# Power_section.net
KiCad netlist of a schematic drawn in Altium Designer
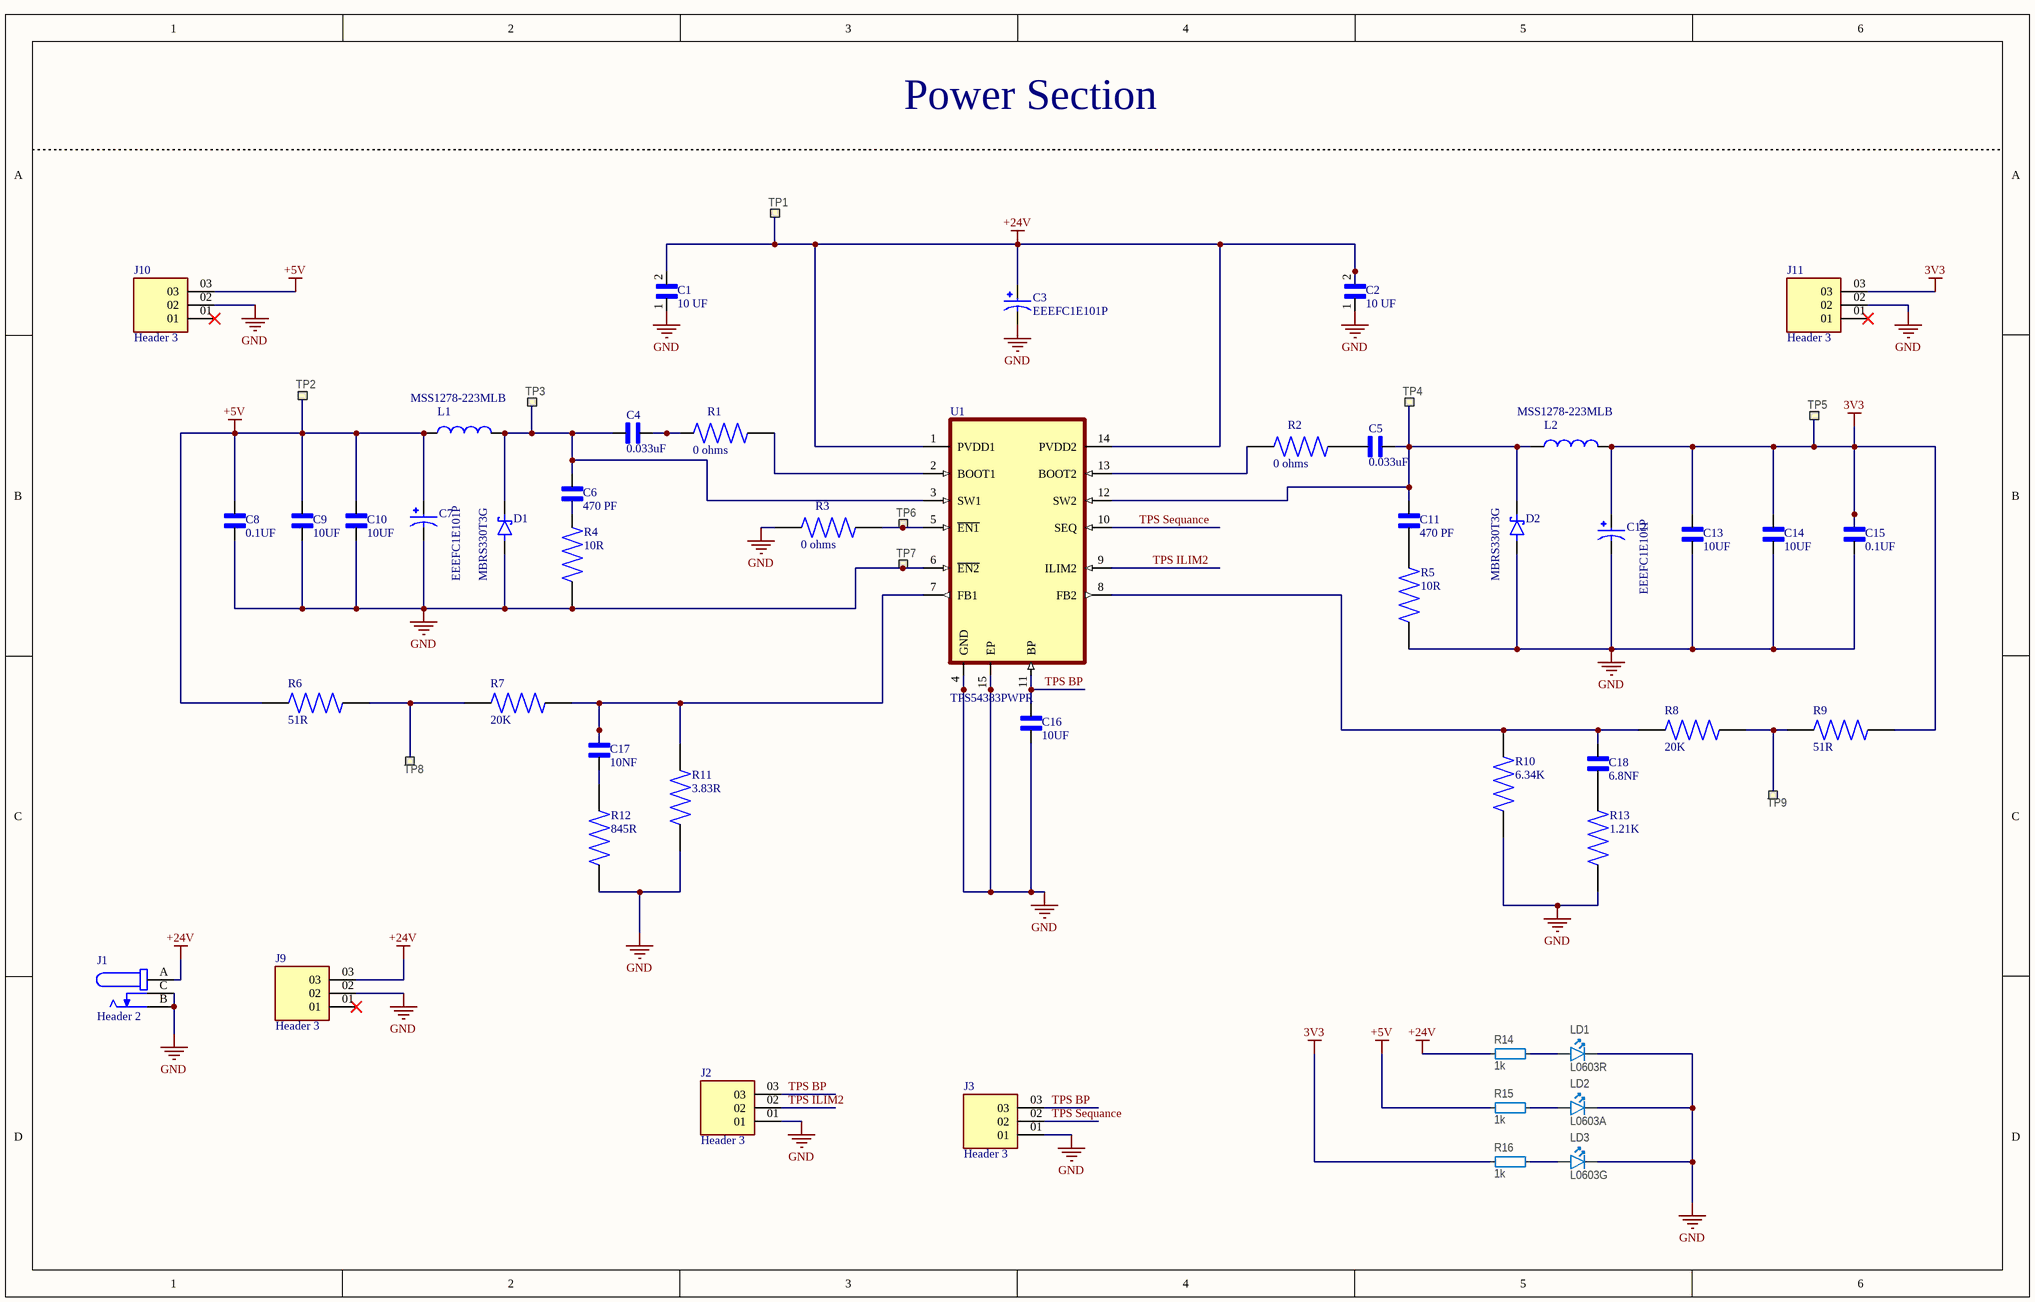
[diagram p0: Power section.SchDoc]

(export (version "E")
  (design (tool "Eeschema 10.0.6"))
  (components
    (comp (ref "C1")
      (value "10 UF")
      (footprint "CAPC3216X180N")
      (description "10礔 卤20% 25V Ceramic Capacitor 1206 (3216 Metric)")
      (fields (field (name "MF") "TDK") (field (name "DIGI-KEY_PART_NUMBER") "445-7708-2-ND"))
      (libsource (lib "C3216X5R1E106M160AB") (part "C3216X5R1E106M160AB"))
    )
    (comp (ref "C2")
      (value "10 UF")
      (footprint "CAPC3216X180N")
      (description "10礔 卤20% 25V Ceramic Capacitor 1206 (3216 Metric)")
      (fields (field (name "MF") "TDK") (field (name "DIGI-KEY_PART_NUMBER") "445-7708-2-ND"))
      (libsource (lib "C3216X5R1E106M160AB") (part "C3216X5R1E106M160AB"))
    )
    (comp (ref "C3")
      (value "EEEFC1E101P")
      (footprint "CAP_EEEFC1E101P")
      (fields (field (name "MF") "Panasonic") (field (name "MP") "EEE-FC1E101P"))
      (libsource (lib "EEEFC1E101P") (part "EEEFC1E101P"))
    )
    (comp (ref "C4")
      (value "0.033uF")
      (footprint "CAPC1608X90")
      (description "Capacitor, ceramic, 25 V, X7R, 20%, .033 μF, 0603")
      (fields (field (name "MF") "KEMET") (field (name "MP") "C0603C104J3RACTU"))
      (libsource (lib "") (part "C0603C104J3RACTU_1"))
    )
    (comp (ref "C5")
      (value "0.033uF")
      (footprint "CAPC1608X90")
      (description "Capacitor, ceramic, 25 V, X7R, 20%, .033 μF, 0603")
      (fields (field (name "MF") "KEMET") (field (name "MP") "C0603C104J3RACTU"))
      (libsource (lib "") (part "C0603C104J3RACTU_1"))
    )
    (comp (ref "C6")
      (value "470 PF")
      (footprint "CAPC1608X90")
      (description "Capacitor, ceramic, 25 V, X7R, 20%, 470 pF, 0603")
      (fields (field (name "MF") "KEMET") (field (name "MP") "C0603C104J3RACTU"))
      (libsource (lib "Accelo Integrated_Library") (part "C0603C104J3RACTU"))
    )
    (comp (ref "C7")
      (value "EEEFC1E101P")
      (footprint "CAP_EEEFC1E101P")
      (fields (field (name "MF") "Panasonic") (field (name "MP") "EEE-FC1E101P"))
      (libsource (lib "EEEFC1E101P") (part "EEEFC1E101P"))
    )
    (comp (ref "C8")
      (value "0.1UF")
      (footprint "CAPC1608X90")
      (description "Capacitor, ceramic, 10 V, X7R, 20%, 0.1 μF, 0603")
      (fields (field (name "MF") "KEMET") (field (name "MP") "C0603C104J3RACTU"))
      (libsource (lib "Accelo Integrated_Library") (part "C0603C104J3RACTU"))
    )
    (comp (ref "C9")
      (value "10UF")
      (footprint "CAPC2012X140N")
      (description "Capacitor, ceramic, 6.3 V, X5R, 20%, 10 μF, 0805")
      (fields (field (name "MF") "AVX") (field (name "MP") "0805ZD474MAT2A"))
      (libsource (lib "0805ZD474MAT2A") (part "0805ZD474MAT2A"))
    )
    (comp (ref "C10")
      (value "10UF")
      (footprint "CAPC2012X140N")
      (description "Capacitor, ceramic, 6.3 V, X5R, 20%, 10 μF, 0805")
      (fields (field (name "MF") "AVX") (field (name "MP") "0805ZD474MAT2A"))
      (libsource (lib "0805ZD474MAT2A") (part "0805ZD474MAT2A"))
    )
    (comp (ref "C11")
      (value "470 PF")
      (footprint "CAPC1608X90")
      (description "Capacitor, ceramic, 25 V, X7R, 20%, 470 pF, 0603")
      (fields (field (name "MF") "KEMET") (field (name "MP") "C0603C104J3RACTU"))
      (libsource (lib "Accelo Integrated_Library") (part "C0603C104J3RACTU"))
    )
    (comp (ref "C12")
      (value "EEEFC1E101P")
      (footprint "CAP_EEEFC1E101P")
      (fields (field (name "MF") "Panasonic") (field (name "MP") "EEE-FC1E101P"))
      (libsource (lib "EEEFC1E101P") (part "EEEFC1E101P"))
    )
    (comp (ref "C13")
      (value "10UF")
      (footprint "CAPC2012X140N")
      (description "Capacitor, ceramic, 6.3 V, X5R, 20%, 10 μF, 0805")
      (fields (field (name "MF") "AVX") (field (name "MP") "0805ZD474MAT2A"))
      (libsource (lib "0805ZD474MAT2A") (part "0805ZD474MAT2A"))
    )
    (comp (ref "C14")
      (value "10UF")
      (footprint "CAPC2012X140N")
      (description "Capacitor, ceramic, 6.3 V, X5R, 20%, 10 μF, 0805")
      (fields (field (name "MF") "AVX") (field (name "MP") "0805ZD474MAT2A"))
      (libsource (lib "0805ZD474MAT2A") (part "0805ZD474MAT2A"))
    )
    (comp (ref "C15")
      (value "0.1UF")
      (footprint "CAPC1608X90")
      (description "Capacitor, ceramic, 10 V, X7R, 20%, 0.1 μF, 0603")
      (fields (field (name "MF") "KEMET") (field (name "MP") "C0603C104J3RACTU"))
      (libsource (lib "Accelo Integrated_Library") (part "C0603C104J3RACTU"))
    )
    (comp (ref "C16")
      (value "10UF")
      (footprint "CAPC2012X140N")
      (description "0.47 ÂµF Â±20% 10V Ceramic Capacitor X5R 0805 (2012 Metric)")
      (fields (field (name "MF") "AVX") (field (name "MP") "0805ZD474MAT2A"))
      (libsource (lib "0805ZD474MAT2A") (part "0805ZD474MAT2A"))
    )
    (comp (ref "C17")
      (value "10NF")
      (footprint "CAPC1608X90")
      (fields (field (name "MF") "KEMET") (field (name "MP") "C0603C104J3RACTU"))
      (libsource (lib "Accelo Integrated_Library") (part "C0603C104J3RACTU"))
    )
    (comp (ref "C18")
      (value "6.8NF")
      (footprint "CAPC1608X90")
      (fields (field (name "MF") "KEMET") (field (name "MP") "C0603C104J3RACTU"))
      (libsource (lib "Accelo Integrated_Library") (part "C0603C104J3RACTU"))
    )
    (comp (ref "D1")
      (value "MBRS330T3G")
      (footprint "DIOM7959X261N")
      (description "Diode Schottky 30 V 3A Surface Mount SMC")
      (fields (field (name "MF") "ON Semiconductor"))
      (libsource (lib "MBRS330T3G") (part "MBRS330T3G"))
    )
    (comp (ref "D2")
      (value "MBRS330T3G")
      (footprint "DIOM7959X261N")
      (description "Diode Schottky 30 V 3A Surface Mount SMC")
      (fields (field (name "MF") "ON Semiconductor"))
      (libsource (lib "MBRS330T3G") (part "MBRS330T3G"))
    )
    (comp (ref "J1")
      (value "Header 2")
      (footprint "TENSILITY_54-00129")
      (description "Connector, dc jack 5.5x2.1 mm, PCB mount, 90 degrees, silver plated, thru hole")
      (fields (field (name "MF") "Tensility International Corp") (field (name "MP") "54-00129"))
      (libsource (lib "54-00129") (part "54-00129"))
    )
    (comp (ref "J2")
      (value "Header 3")
      (footprint "SAMTEC_HMTSW-103-XX-X-S-XXX")
      (description "Connector Unshrouded Header 3 Position 2.54mm Solder Straight Through Hole")
      (fields (field (name "MF") "Samtec") (field (name "MP") "HMTSW-103-10-T-S-330"))
      (libsource (lib "Accelo Integrated_Library") (part "HMTSW-103-XX-X-S-XXX"))
    )
    (comp (ref "J3")
      (value "Header 3")
      (footprint "SAMTEC_HMTSW-103-XX-X-S-XXX")
      (description "Connector Unshrouded Header 3 Position 2.54mm Solder Straight Through Hole")
      (fields (field (name "MF") "Samtec") (field (name "MP") "HMTSW-103-10-T-S-330"))
      (libsource (lib "Accelo Integrated_Library") (part "HMTSW-103-XX-X-S-XXX"))
    )
    (comp (ref "J9")
      (value "Header 3")
      (footprint "SAMTEC_HMTSW-103-XX-X-S-XXX")
      (description "Connector Unshrouded Header 3 Position 2.54mm Solder Straight Through Hole")
      (fields (field (name "MF") "Samtec") (field (name "MP") "HMTSW-103-10-T-S-330"))
      (libsource (lib "Accelo Integrated_Library") (part "HMTSW-103-XX-X-S-XXX"))
    )
    (comp (ref "J10")
      (value "Header 3")
      (footprint "SAMTEC_HMTSW-103-XX-X-S-XXX")
      (description "Connector Unshrouded Header 3 Position 2.54mm Solder Straight Through Hole")
      (fields (field (name "MF") "Samtec") (field (name "MP") "HMTSW-103-10-T-S-330"))
      (libsource (lib "Accelo Integrated_Library") (part "HMTSW-103-XX-X-S-XXX"))
    )
    (comp (ref "J11")
      (value "Header 3")
      (footprint "SAMTEC_HMTSW-103-XX-X-S-XXX")
      (description "Connector Unshrouded Header 3 Position 2.54mm Solder Straight Through Hole")
      (fields (field (name "MF") "Samtec") (field (name "MP") "HMTSW-103-10-T-S-330"))
      (libsource (lib "Accelo Integrated_Library") (part "HMTSW-103-XX-X-S-XXX"))
    )
    (comp (ref "L1")
      (value "MSS1278-223MLB")
      (footprint "IND_MSS1278-223MLB")
      (description "Fixed Inductors 22uH Shld 20% 4A 39.5mOhms AECQ2")
      (fields (field (name "MF") "Coilcraft"))
      (libsource (lib "MSS1278-223MLB") (part "MSS1278-223MLB"))
    )
    (comp (ref "L2")
      (value "MSS1278-223MLB")
      (footprint "IND_MSS1278-223MLB")
      (description "Fixed Inductors 22uH Shld 20% 4A 39.5mOhms AECQ2")
      (fields (field (name "MF") "Coilcraft"))
      (libsource (lib "MSS1278-223MLB") (part "MSS1278-223MLB"))
    )
    (comp (ref "LD1")
      (value "L0603R")
      (footprint "LED_0603_R")
      (description "LED, Red, 0603, Vf=2V, - 40 to +100°C")
      (fields
        (field (name "PART NUMBER") "ASMT-RR45-AQ902")
        (field (name "MANUFACTURER") "Avago")
        (field (name "AUTHOR") "rsk")
      )
      (libsource (lib "pca10152") (part "ASMT-RR45-AQ902"))
    )
    (comp (ref "LD2")
      (value "L0603A")
      (footprint "LED_0603_Y")
      (description "LED, Amber, 0603,  Vf=2V, - 40 to +100°C")
      (fields
        (field (name "PART NUMBER") "ASMT-RA45-AP932")
        (field (name "MANUFACTURER") "Avago")
        (field (name "AUTHOR") "rsk")
      )
      (libsource (lib "pca10152") (part "ASMT-RA45-AP932"))
    )
    (comp (ref "LD3")
      (value "L0603G")
      (footprint "LED_0603_G")
      (description "LED, Yellow Green, 0603, Vf=2V, - 40 to +100°C")
      (fields
        (field (name "PART NUMBER") "ASMT-RF45-AN002")
        (field (name "MANUFACTURER") "Avago")
        (field (name "AUTHOR") "rsk")
      )
      (libsource (lib "pca10152") (part "ASMT-RF45-AN002"))
    )
    (comp (ref "R1")
      (value "0 ohms")
      (footprint "RESC1608X55N")
      (description "Resistor, chip, 1/16 W, 5%, 0 Ω, 0603")
      (fields (field (name "MF") "Yageo") (field (name "MP") "RC0603JR-0751RL"))
      (libsource (lib "RC0603JR-0751RL") (part "RC0603JR-0751RL"))
    )
    (comp (ref "R2")
      (value "0 ohms")
      (footprint "RESC1608X55N")
      (description "Resistor, chip, 1/16 W, 5%, 0 Ω, 0603")
      (fields (field (name "MF") "Yageo") (field (name "MP") "RC0603JR-0751RL"))
      (libsource (lib "RC0603JR-0751RL") (part "RC0603JR-0751RL"))
    )
    (comp (ref "R3")
      (value "0 ohms")
      (footprint "RESC1608X55N")
      (description "Resistor, chip, 1/16 W, 5%, 0 Ω, 0603")
      (fields (field (name "MF") "Yageo") (field (name "MP") "RC0603JR-0751RL"))
      (libsource (lib "RC0603JR-0751RL") (part "RC0603JR-0751RL"))
    )
    (comp (ref "R4")
      (value "10R")
      (footprint "RESC1608X55N")
      (description "Resistor, chip, 1/16 W, 5%, 10 Ω, 0603")
      (fields (field (name "MF") "Yageo") (field (name "MP") "RC0603JR-0751RL"))
      (libsource (lib "RC0603JR-0751RL") (part "RC0603JR-0751RL"))
    )
    (comp (ref "R5")
      (value "10R")
      (footprint "RESC1608X55N")
      (description "Resistor, chip, 1/16 W, 5%, 10 Ω, 0603")
      (fields (field (name "MF") "Yageo") (field (name "MP") "RC0603JR-0751RL"))
      (libsource (lib "RC0603JR-0751RL") (part "RC0603JR-0751RL"))
    )
    (comp (ref "R6")
      (value "51R")
      (footprint "RESC1608X55N")
      (description "51 Ohms Â±5% 0.1W, 1/10W Chip Resistor 0603 (1608 Metric) Moisture Resistant Thick Film")
      (fields (field (name "MF") "Yageo") (field (name "MP") "RC0603JR-0751RL"))
      (libsource (lib "RC0603JR-0751RL") (part "RC0603JR-0751RL"))
    )
    (comp (ref "R7")
      (value "20K")
      (footprint "RESC1608X55N")
      (description "51 Ohms Â±5% 0.1W, 1/10W Chip Resistor 0603 (1608 Metric) Moisture Resistant Thick Film")
      (fields (field (name "MF") "Yageo") (field (name "MP") "RC0603JR-0751RL"))
      (libsource (lib "RC0603JR-0751RL") (part "RC0603JR-0751RL"))
    )
    (comp (ref "R8")
      (value "20K")
      (footprint "RESC1608X55N")
      (description "51 Ohms Â±5% 0.1W, 1/10W Chip Resistor 0603 (1608 Metric) Moisture Resistant Thick Film")
      (fields (field (name "MF") "Yageo") (field (name "MP") "RC0603JR-0751RL"))
      (libsource (lib "RC0603JR-0751RL") (part "RC0603JR-0751RL"))
    )
    (comp (ref "R9")
      (value "51R")
      (footprint "RESC1608X55N")
      (description "51 Ohms Â±5% 0.1W, 1/10W Chip Resistor 0603 (1608 Metric) Moisture Resistant Thick Film")
      (fields (field (name "MF") "Yageo") (field (name "MP") "RC0603JR-0751RL"))
      (libsource (lib "RC0603JR-0751RL") (part "RC0603JR-0751RL"))
    )
    (comp (ref "R10")
      (value "6.34K")
      (footprint "RESC1608X55N")
      (description "51 Ohms Â±5% 0.1W, 1/10W Chip Resistor 0603 (1608 Metric) Moisture Resistant Thick Film")
      (fields (field (name "MF") "Yageo") (field (name "MP") "RC0603JR-0751RL"))
      (libsource (lib "RC0603JR-0751RL") (part "RC0603JR-0751RL"))
    )
    (comp (ref "R11")
      (value "3.83R")
      (footprint "RESC1608X55N")
      (description "51 Ohms Â±5% 0.1W, 1/10W Chip Resistor 0603 (1608 Metric) Moisture Resistant Thick Film")
      (fields (field (name "MF") "Yageo") (field (name "MP") "RC0603JR-0751RL"))
      (libsource (lib "RC0603JR-0751RL") (part "RC0603JR-0751RL"))
    )
    (comp (ref "R12")
      (value "845R")
      (footprint "RESC1608X55N")
      (description "51 Ohms Â±5% 0.1W, 1/10W Chip Resistor 0603 (1608 Metric) Moisture Resistant Thick Film")
      (fields (field (name "MF") "Yageo") (field (name "MP") "RC0603JR-0751RL"))
      (libsource (lib "RC0603JR-0751RL") (part "RC0603JR-0751RL"))
    )
    (comp (ref "R13")
      (value "1.21K")
      (footprint "RESC1608X55N")
      (description "51 Ohms Â±5% 0.1W, 1/10W Chip Resistor 0603 (1608 Metric) Moisture Resistant Thick Film")
      (fields (field (name "MF") "Yageo") (field (name "MP") "RC0603JR-0751RL"))
      (libsource (lib "RC0603JR-0751RL") (part "RC0603JR-0751RL"))
    )
    (comp (ref "R14")
      (value "1k")
      (footprint "RESC0603X03L_C")
      (description "Resistor, ±1%, 0.05W")
      (fields
        (field (name "PART NUMBER") "R0201-1k0")
        (field (name "MANUFACTURER") "N.A.")
        (field (name "AUTHOR") "rsk")
      )
      (libsource (lib "pca10152") (part "R0201-1k0"))
    )
    (comp (ref "R15")
      (value "1k")
      (footprint "RESC0603X03L_C")
      (description "Resistor, ±1%, 0.05W")
      (fields
        (field (name "PART NUMBER") "R0201-1k0")
        (field (name "MANUFACTURER") "N.A.")
        (field (name "AUTHOR") "rsk")
      )
      (libsource (lib "pca10152") (part "R0201-1k0"))
    )
    (comp (ref "R16")
      (value "1k")
      (footprint "RESC0603X03L_C")
      (description "Resistor, ±1%, 0.05W")
      (fields
        (field (name "PART NUMBER") "R0201-1k0")
        (field (name "MANUFACTURER") "N.A.")
        (field (name "AUTHOR") "rsk")
      )
      (libsource (lib "pca10152") (part "R0201-1k0"))
    )
    (comp (ref "TP1")
      (value "Ø0.7mm,SMD")
      (footprint "TP_SMD_D0.7mm")
      (description "0.7mm circular SMD testpad")
      (fields
        (field (name "PART NUMBER") "TP_SMD_Ø0.7MM")
        (field (name "MANUFACTURER") "Nordic Semiconductor")
        (field (name "AUTHOR") "rsk")
      )
      (libsource (lib "") (part "TP_SMD_Ø0.7MM_1"))
    )
    (comp (ref "TP2")
      (value "Ø0.7mm,SMD")
      (footprint "TP_SMD_D0.7mm")
      (description "0.7mm circular SMD testpad")
      (fields
        (field (name "PART NUMBER") "TP_SMD_Ø0.7MM")
        (field (name "MANUFACTURER") "Nordic Semiconductor")
        (field (name "AUTHOR") "rsk")
      )
      (libsource (lib "") (part "TP_SMD_Ø0.7MM_1"))
    )
    (comp (ref "TP3")
      (value "Ø0.7mm,SMD")
      (footprint "TP_SMD_D0.7mm")
      (description "0.7mm circular SMD testpad")
      (fields
        (field (name "PART NUMBER") "TP_SMD_Ø0.7MM")
        (field (name "MANUFACTURER") "Nordic Semiconductor")
        (field (name "AUTHOR") "rsk")
      )
      (libsource (lib "") (part "TP_SMD_Ø0.7MM_1"))
    )
    (comp (ref "TP4")
      (value "Ø0.7mm,SMD")
      (footprint "TP_SMD_D0.7mm")
      (description "0.7mm circular SMD testpad")
      (fields
        (field (name "PART NUMBER") "TP_SMD_Ø0.7MM")
        (field (name "MANUFACTURER") "Nordic Semiconductor")
        (field (name "AUTHOR") "rsk")
      )
      (libsource (lib "") (part "TP_SMD_Ø0.7MM_1"))
    )
    (comp (ref "TP5")
      (value "Ø0.7mm,SMD")
      (footprint "TP_SMD_D0.7mm")
      (description "0.7mm circular SMD testpad")
      (fields
        (field (name "PART NUMBER") "TP_SMD_Ø0.7MM")
        (field (name "MANUFACTURER") "Nordic Semiconductor")
        (field (name "AUTHOR") "rsk")
      )
      (libsource (lib "") (part "TP_SMD_Ø0.7MM_1"))
    )
    (comp (ref "TP6")
      (value "Ø0.7mm,SMD")
      (footprint "TP_SMD_D0.7mm")
      (description "0.7mm circular SMD testpad")
      (fields
        (field (name "PART NUMBER") "TP_SMD_Ø0.7MM")
        (field (name "MANUFACTURER") "Nordic Semiconductor")
        (field (name "AUTHOR") "rsk")
      )
      (libsource (lib "") (part "TP_SMD_Ø0.7MM_1"))
    )
    (comp (ref "TP7")
      (value "Ø0.7mm,SMD")
      (footprint "TP_SMD_D0.7mm")
      (description "0.7mm circular SMD testpad")
      (fields
        (field (name "PART NUMBER") "TP_SMD_Ø0.7MM")
        (field (name "MANUFACTURER") "Nordic Semiconductor")
        (field (name "AUTHOR") "rsk")
      )
      (libsource (lib "") (part "TP_SMD_Ø0.7MM_1"))
    )
    (comp (ref "TP8")
      (value "Ø0.7mm,SMD")
      (footprint "TP_SMD_D0.7mm")
      (description "0.7mm circular SMD testpad")
      (fields
        (field (name "PART NUMBER") "TP_SMD_Ø0.7MM")
        (field (name "MANUFACTURER") "Nordic Semiconductor")
        (field (name "AUTHOR") "rsk")
      )
      (libsource (lib "pca10152") (part "TP_SMD_Ø0.7MM"))
    )
    (comp (ref "TP9")
      (value "Ø0.7mm,SMD")
      (footprint "TP_SMD_D0.7mm")
      (description "0.7mm circular SMD testpad")
      (fields
        (field (name "PART NUMBER") "TP_SMD_Ø0.7MM")
        (field (name "MANUFACTURER") "Nordic Semiconductor")
        (field (name "AUTHOR") "rsk")
      )
      (libsource (lib "pca10152") (part "TP_SMD_Ø0.7MM"))
    )
    (comp (ref "U1")
      (value "TPS54383PWPR")
      (footprint "IC_TPS27S100BPWPR")
      (fields (field (name "MF") "{'manufacturer': u'Texas Instruments'}"))
      (libsource (lib "TP") (part "TPS54383PWPR"))
    )
  )
  (nets
    (net (code "1") (name "+5V") (class "Default")
      (node (ref "C10") (pin "1") (pinfunction "1_1") (pintype "passive"))
      (node (ref "C7") (pin "1") (pinfunction "1_1") (pintype "passive"))
      (node (ref "C8") (pin "1") (pinfunction "1_1") (pintype "passive"))
      (node (ref "C9") (pin "1") (pinfunction "1_1") (pintype "passive"))
      (node (ref "J10") (pin "03") (pinfunction "03_03") (pintype "passive"))
      (node (ref "L1") (pin "1") (pinfunction "1_1") (pintype "passive"))
      (node (ref "R15") (pin "1") (pinfunction "1_1") (pintype "passive"))
      (node (ref "R6") (pin "2") (pinfunction "2_2") (pintype "passive"))
      (node (ref "TP2") (pin "1") (pinfunction "1_1") (pintype "passive"))
    )
    (net (code "2") (name "+24V") (class "Default")
      (node (ref "C1") (pin "2") (pinfunction "2_2") (pintype "passive"))
      (node (ref "C2") (pin "2") (pinfunction "2_2") (pintype "passive"))
      (node (ref "C3") (pin "1") (pinfunction "1_1") (pintype "passive"))
      (node (ref "J1") (pin "A") (pinfunction "A_A") (pintype "passive"))
      (node (ref "J9") (pin "03") (pinfunction "03_03") (pintype "passive"))
      (node (ref "R14") (pin "1") (pinfunction "1_1") (pintype "passive"))
      (node (ref "TP1") (pin "1") (pinfunction "1_1") (pintype "passive"))
      (node (ref "U1") (pin "1") (pinfunction "PVDD1_1") (pintype "power_in"))
      (node (ref "U1") (pin "14") (pinfunction "PVDD2_14") (pintype "power_in"))
    )
    (net (code "3") (name "/TPS BP") (class "Default")
      (node (ref "C16") (pin "1") (pinfunction "1_1") (pintype "passive"))
      (node (ref "J2") (pin "03") (pinfunction "03_03") (pintype "passive"))
      (node (ref "J3") (pin "03") (pinfunction "03_03") (pintype "passive"))
      (node (ref "U1") (pin "11") (pinfunction "BP_11") (pintype "input"))
    )
    (net (code "4") (name "/TPS ILIM2") (class "Default")
      (node (ref "J2") (pin "02") (pinfunction "02_02") (pintype "passive"))
      (node (ref "U1") (pin "9") (pinfunction "ILIM2_9") (pintype "input"))
    )
    (net (code "5") (name "/TPS Sequance") (class "Default")
      (node (ref "J3") (pin "02") (pinfunction "02_02") (pintype "passive"))
      (node (ref "U1") (pin "10") (pinfunction "SEQ_10") (pintype "input"))
    )
    (net (code "6") (name "3V3") (class "Default")
      (node (ref "C12") (pin "1") (pinfunction "1_1") (pintype "passive"))
      (node (ref "C13") (pin "1") (pinfunction "1_1") (pintype "passive"))
      (node (ref "C14") (pin "1") (pinfunction "1_1") (pintype "passive"))
      (node (ref "C15") (pin "1") (pinfunction "1_1") (pintype "passive"))
      (node (ref "J11") (pin "03") (pinfunction "03_03") (pintype "passive"))
      (node (ref "L2") (pin "2") (pinfunction "2_2") (pintype "passive"))
      (node (ref "R16") (pin "1") (pinfunction "1_1") (pintype "passive"))
      (node (ref "R9") (pin "1") (pinfunction "1_1") (pintype "passive"))
      (node (ref "TP5") (pin "1") (pinfunction "1_1") (pintype "passive"))
    )
    (net (code "7") (name "GND") (class "Default")
      (node (ref "C1") (pin "1") (pinfunction "1_1") (pintype "passive"))
      (node (ref "C10") (pin "2") (pinfunction "2_2") (pintype "passive"))
      (node (ref "C12") (pin "2") (pinfunction "2_2") (pintype "passive"))
      (node (ref "C13") (pin "2") (pinfunction "2_2") (pintype "passive"))
      (node (ref "C14") (pin "2") (pinfunction "2_2") (pintype "passive"))
      (node (ref "C15") (pin "2") (pinfunction "2_2") (pintype "passive"))
      (node (ref "C16") (pin "2") (pinfunction "2_2") (pintype "passive"))
      (node (ref "C2") (pin "1") (pinfunction "1_1") (pintype "passive"))
      (node (ref "C3") (pin "2") (pinfunction "2_2") (pintype "passive"))
      (node (ref "C7") (pin "2") (pinfunction "2_2") (pintype "passive"))
      (node (ref "C8") (pin "2") (pinfunction "2_2") (pintype "passive"))
      (node (ref "C9") (pin "2") (pinfunction "2_2") (pintype "passive"))
      (node (ref "D1") (pin "A") (pinfunction "A_A") (pintype "passive"))
      (node (ref "D2") (pin "A") (pinfunction "A_A") (pintype "passive"))
      (node (ref "J1") (pin "B") (pinfunction "B_B") (pintype "passive"))
      (node (ref "J1") (pin "C") (pinfunction "C_C") (pintype "passive"))
      (node (ref "J10") (pin "02") (pinfunction "02_02") (pintype "passive"))
      (node (ref "J11") (pin "02") (pinfunction "02_02") (pintype "passive"))
      (node (ref "J2") (pin "01") (pinfunction "01_01") (pintype "passive"))
      (node (ref "J3") (pin "01") (pinfunction "01_01") (pintype "passive"))
      (node (ref "J9") (pin "02") (pinfunction "02_02") (pintype "passive"))
      (node (ref "LD1") (pin "1") (pinfunction "C_1") (pintype "passive"))
      (node (ref "LD2") (pin "1") (pinfunction "C_1") (pintype "passive"))
      (node (ref "LD3") (pin "1") (pinfunction "C_1") (pintype "passive"))
      (node (ref "R10") (pin "1") (pinfunction "1_1") (pintype "passive"))
      (node (ref "R11") (pin "1") (pinfunction "1_1") (pintype "passive"))
      (node (ref "R12") (pin "1") (pinfunction "1_1") (pintype "passive"))
      (node (ref "R13") (pin "1") (pinfunction "1_1") (pintype "passive"))
      (node (ref "R3") (pin "1") (pinfunction "1_1") (pintype "passive"))
      (node (ref "R4") (pin "1") (pinfunction "1_1") (pintype "passive"))
      (node (ref "R5") (pin "1") (pinfunction "1_1") (pintype "passive"))
      (node (ref "TP7") (pin "1") (pinfunction "1_1") (pintype "passive"))
      (node (ref "U1") (pin "15") (pinfunction "EP_15") (pintype "power_in"))
      (node (ref "U1") (pin "4") (pinfunction "GND_4") (pintype "power_in"))
      (node (ref "U1") (pin "6") (pinfunction "~{EN2}_6") (pintype "input"))
    )
    (net (code "8") (name "Net-(C4-Pad1)") (class "Default")
      (node (ref "C4") (pin "1") (pinfunction "1_1") (pintype "passive"))
      (node (ref "R1") (pin "1") (pinfunction "1_1") (pintype "passive"))
    )
    (net (code "9") (name "Net-(C5-Pad2)") (class "Default")
      (node (ref "C5") (pin "2") (pinfunction "2_2") (pintype "passive"))
      (node (ref "R2") (pin "2") (pinfunction "2_2") (pintype "passive"))
    )
    (net (code "10") (name "Net-(C6-Pad2)") (class "Default")
      (node (ref "C6") (pin "2") (pinfunction "2_2") (pintype "passive"))
      (node (ref "R4") (pin "2") (pinfunction "2_2") (pintype "passive"))
    )
    (net (code "11") (name "Net-(C11-Pad2)") (class "Default")
      (node (ref "C11") (pin "2") (pinfunction "2_2") (pintype "passive"))
      (node (ref "R5") (pin "2") (pinfunction "2_2") (pintype "passive"))
    )
    (net (code "12") (name "Net-(C17-Pad2)") (class "Default")
      (node (ref "C17") (pin "2") (pinfunction "2_2") (pintype "passive"))
      (node (ref "R12") (pin "2") (pinfunction "2_2") (pintype "passive"))
    )
    (net (code "13") (name "Net-(C18-Pad2)") (class "Default")
      (node (ref "C18") (pin "2") (pinfunction "2_2") (pintype "passive"))
      (node (ref "R13") (pin "2") (pinfunction "2_2") (pintype "passive"))
    )
    (net (code "14") (name "Net-(D1-K)") (class "Default")
      (node (ref "C4") (pin "2") (pinfunction "2_2") (pintype "passive"))
      (node (ref "C6") (pin "1") (pinfunction "1_1") (pintype "passive"))
      (node (ref "D1") (pin "C") (pinfunction "K_C") (pintype "passive"))
      (node (ref "L1") (pin "2") (pinfunction "2_2") (pintype "passive"))
      (node (ref "TP3") (pin "1") (pinfunction "1_1") (pintype "passive"))
      (node (ref "U1") (pin "3") (pinfunction "SW1_3") (pintype "input"))
    )
    (net (code "15") (name "Net-(D2-K)") (class "Default")
      (node (ref "C11") (pin "1") (pinfunction "1_1") (pintype "passive"))
      (node (ref "C5") (pin "1") (pinfunction "1_1") (pintype "passive"))
      (node (ref "D2") (pin "C") (pinfunction "K_C") (pintype "passive"))
      (node (ref "L2") (pin "1") (pinfunction "1_1") (pintype "passive"))
      (node (ref "TP4") (pin "1") (pinfunction "1_1") (pintype "passive"))
      (node (ref "U1") (pin "12") (pinfunction "SW2_12") (pintype "input"))
    )
    (net (code "16") (name "Net-(LD1-A)") (class "Default")
      (node (ref "LD1") (pin "2") (pinfunction "A_2") (pintype "passive"))
      (node (ref "R14") (pin "2") (pinfunction "2_2") (pintype "passive"))
    )
    (net (code "17") (name "Net-(LD2-A)") (class "Default")
      (node (ref "LD2") (pin "2") (pinfunction "A_2") (pintype "passive"))
      (node (ref "R15") (pin "2") (pinfunction "2_2") (pintype "passive"))
    )
    (net (code "18") (name "Net-(LD3-A)") (class "Default")
      (node (ref "LD3") (pin "2") (pinfunction "A_2") (pintype "passive"))
      (node (ref "R16") (pin "2") (pinfunction "2_2") (pintype "passive"))
    )
    (net (code "19") (name "Net-(R6-Pad1)") (class "Default")
      (node (ref "R6") (pin "1") (pinfunction "1_1") (pintype "passive"))
      (node (ref "R7") (pin "2") (pinfunction "2_2") (pintype "passive"))
      (node (ref "TP8") (pin "1") (pinfunction "1_1") (pintype "passive"))
    )
    (net (code "20") (name "Net-(R8-Pad1)") (class "Default")
      (node (ref "R8") (pin "1") (pinfunction "1_1") (pintype "passive"))
      (node (ref "R9") (pin "2") (pinfunction "2_2") (pintype "passive"))
      (node (ref "TP9") (pin "1") (pinfunction "1_1") (pintype "passive"))
    )
    (net (code "21") (name "Net-(U1-BOOT1)") (class "Default")
      (node (ref "R1") (pin "2") (pinfunction "2_2") (pintype "passive"))
      (node (ref "U1") (pin "2") (pinfunction "BOOT1_2") (pintype "input"))
    )
    (net (code "22") (name "Net-(U1-BOOT2)") (class "Default")
      (node (ref "R2") (pin "1") (pinfunction "1_1") (pintype "passive"))
      (node (ref "U1") (pin "13") (pinfunction "BOOT2_13") (pintype "input"))
    )
    (net (code "23") (name "Net-(U1-FB1)") (class "Default")
      (node (ref "C17") (pin "1") (pinfunction "1_1") (pintype "passive"))
      (node (ref "R11") (pin "2") (pinfunction "2_2") (pintype "passive"))
      (node (ref "R7") (pin "1") (pinfunction "1_1") (pintype "passive"))
      (node (ref "U1") (pin "7") (pinfunction "FB1_7") (pintype "output"))
    )
    (net (code "24") (name "Net-(U1-FB2)") (class "Default")
      (node (ref "C18") (pin "1") (pinfunction "1_1") (pintype "passive"))
      (node (ref "R10") (pin "2") (pinfunction "2_2") (pintype "passive"))
      (node (ref "R8") (pin "2") (pinfunction "2_2") (pintype "passive"))
      (node (ref "U1") (pin "8") (pinfunction "FB2_8") (pintype "output"))
    )
    (net (code "25") (name "Net-(U1-~{EN1})") (class "Default")
      (node (ref "R3") (pin "2") (pinfunction "2_2") (pintype "passive"))
      (node (ref "TP6") (pin "1") (pinfunction "1_1") (pintype "passive"))
      (node (ref "U1") (pin "5") (pinfunction "~{EN1}_5") (pintype "input"))
    )
    (net (code "26") (name "unconnected-(J9-Pad01)") (class "Default")
      (node (ref "J9") (pin "01") (pinfunction "01_01") (pintype "passive+no_connect"))
    )
    (net (code "27") (name "unconnected-(J10-Pad01)") (class "Default")
      (node (ref "J10") (pin "01") (pinfunction "01_01") (pintype "passive+no_connect"))
    )
    (net (code "28") (name "unconnected-(J11-Pad01)") (class "Default")
      (node (ref "J11") (pin "01") (pinfunction "01_01") (pintype "passive+no_connect"))
    )
  )
)
